# DXP_LCD1602.net
KiCad netlist of a schematic drawn in Altium Designer
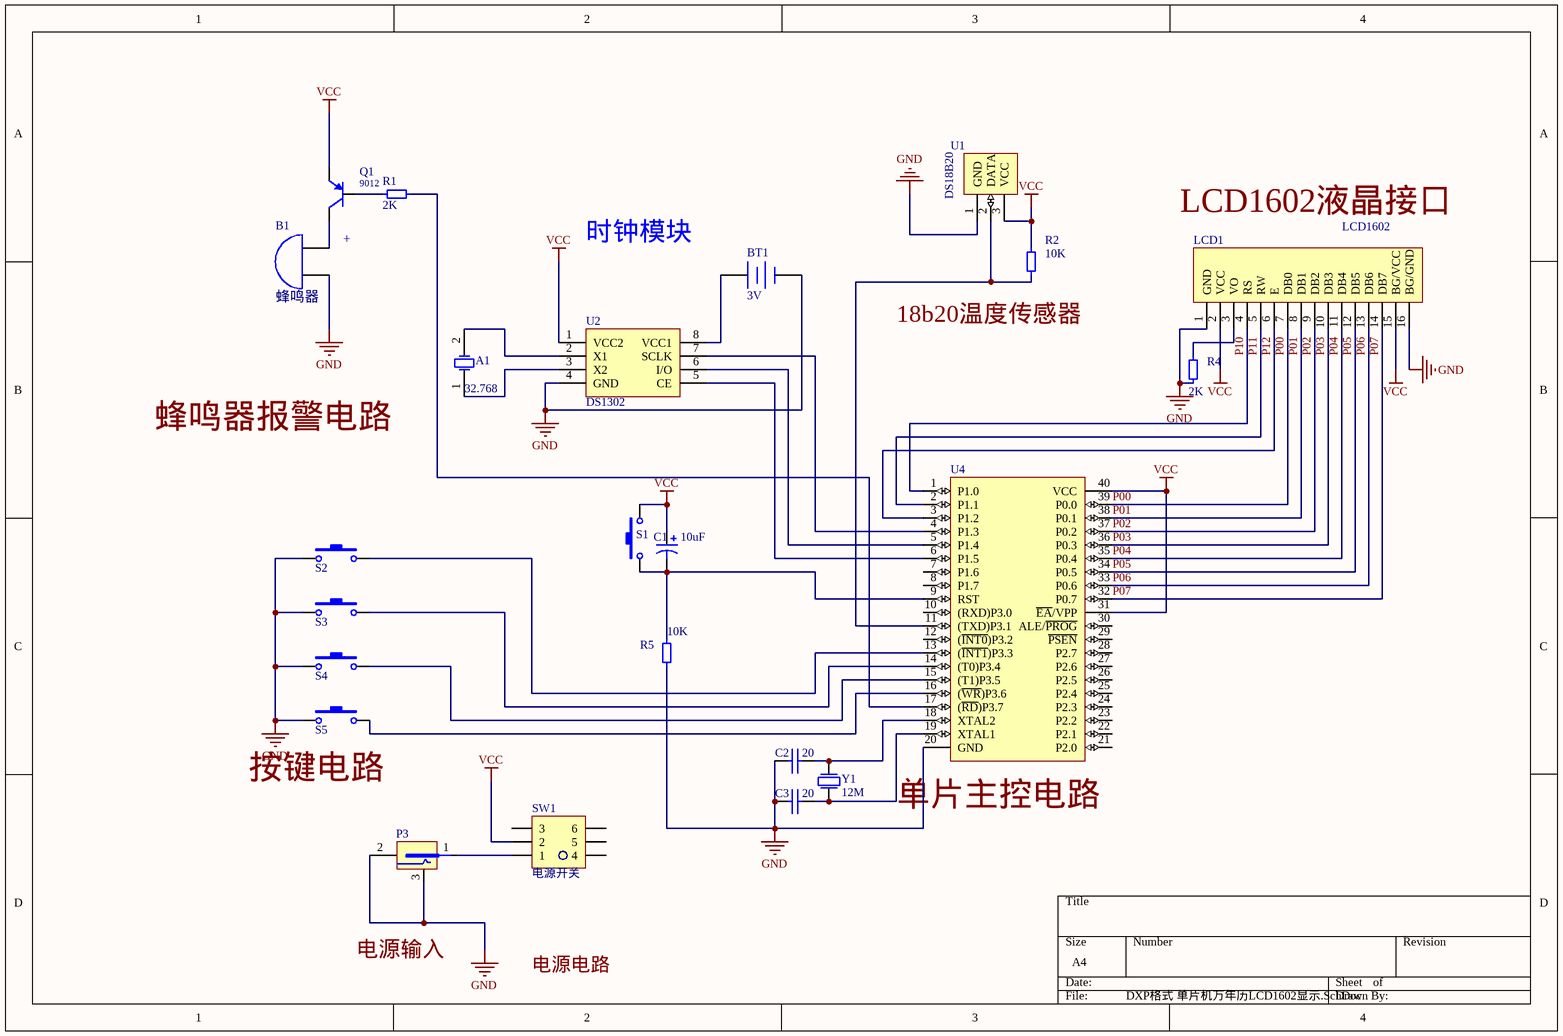
[diagram p0: DXP格式 单片机万年历LCD1602显示.SchDoc]

(export (version "E")
  (design (tool "Eeschema 10.0.6"))
  (components
    (comp (ref "A1") (value "32.768") (footprint "HDR1X2") (libsource (lib "实用原理图库") (part "XTA")))
    (comp (ref "B1")
      (value "蜂鸣器")
      (footprint "Bett")
      (description "Bell")
      (libsource (lib "实验板原理图") (part "BELL"))
    )
    (comp (ref "BT1")
      (value "3V")
      (footprint "BATT")
      (description "Multicell Battery")
      (fields (field (name "PUBLISHER") "Altium Limited"))
      (libsource (lib "Miscellaneous Devices") (part "Battery"))
    )
    (comp (ref "C1")
      (value "10uF")
      (footprint "C_10")
      (description "Polarized Capacitor (Radial)")
      (fields (field (name "PUBLISHER") "Altium Limited"))
      (libsource (lib "简易动环监控系统") (part "Cap Pol1"))
    )
    (comp (ref "C2")
      (value "20")
      (footprint "CAP5")
      (description "电容")
      (libsource (lib "C8051F020最小2") (part "CAP"))
    )
    (comp (ref "C3")
      (value "20")
      (footprint "CAP5")
      (description "电容")
      (libsource (lib "C8051F020最小2") (part "CAP"))
    )
    (comp (ref "LCD1") (value "LCD1602") (footprint "1602") (libsource (lib "实用原理图库") (part "LCD1602")))
    (comp (ref "P3") (value "电源输入") (footprint "DC2.1") (libsource (lib "我自己的") (part "POWER")))
    (comp (ref "Q1")
      (value "9012")
      (footprint "s三极管直插")
      (description "PNP General Purpose Amplifier")
      (fields (field (name "PUBLISHER") "Altium Limited"))
      (libsource (lib "实验板原理图") (part "2N3906"))
    )
    (comp (ref "R1") (value "2K") (footprint "AXIAL0.3") (libsource (lib "C8051F020最小2") (part "RES2")))
    (comp (ref "R2") (value "10K") (footprint "AXIAL0.3") (libsource (lib "C8051F020最小2") (part "RES2")))
    (comp (ref "R4") (value "2K") (footprint "AXIAL0.3") (libsource (lib "C8051F020最小2") (part "RES2")))
    (comp (ref "R5") (value "10K") (footprint "res400mil") (libsource (lib "C8051F020最小2") (part "RES2")))
    (comp (ref "S1")
      (value "SW-PB")
      (footprint "key")
      (description "Switch")
      (fields (field (name "PUBLISHER") "Altium Limited"))
      (libsource (lib "实验板原理图") (part "SW-PB"))
    )
    (comp (ref "S2")
      (value "SW-PB")
      (footprint "key")
      (description "Switch")
      (fields (field (name "PUBLISHER") "Altium Limited"))
      (libsource (lib "实验板原理图") (part "SW-PB"))
    )
    (comp (ref "S3")
      (value "SW-PB")
      (footprint "key")
      (description "Switch")
      (fields (field (name "PUBLISHER") "Altium Limited"))
      (libsource (lib "实验板原理图") (part "SW-PB"))
    )
    (comp (ref "S4")
      (value "SW-PB")
      (footprint "key")
      (description "Switch")
      (fields (field (name "PUBLISHER") "Altium Limited"))
      (libsource (lib "实验板原理图") (part "SW-PB"))
    )
    (comp (ref "S5")
      (value "SW-PB")
      (footprint "key")
      (description "Switch")
      (fields (field (name "PUBLISHER") "Altium Limited"))
      (libsource (lib "实验板原理图") (part "SW-PB"))
    )
    (comp (ref "SW1") (value "电源开关") (footprint "sw_自锁 1") (libsource (lib "我自己的") (part "SW1")))
    (comp (ref "U1") (value "DS18B20") (footprint "18B20") (libsource (lib "实验板原理图") (part "DS18B20")))
    (comp (ref "U2") (value "DS1302") (footprint "DIP8") (libsource (lib "实用原理图库") (part "DS1302")))
    (comp (ref "U4") (value "STC89C52") (footprint "DIP40 - 做板") (libsource (lib "实验板原理图") (part "U1")))
    (comp (ref "Y1")
      (value "12M")
      (footprint "XTAL")
      (description "Crystal Oscillator")
      (libsource (lib "C8051F020最小2") (part "16M"))
    )
  )
  (nets
    (net (code "3") (name "/P00") (class "Default")
      (node (ref "LCD1") (pin "7") (pinfunction "DB0_7") (pintype "passive"))
      (node (ref "U4") (pin "39") (pinfunction "P0.0_39") (pintype "bidirectional"))
    )
    (net (code "4") (name "/P01") (class "Default")
      (node (ref "LCD1") (pin "8") (pinfunction "DB1_8") (pintype "passive"))
      (node (ref "U4") (pin "38") (pinfunction "P0.1_38") (pintype "bidirectional"))
    )
    (net (code "5") (name "/P02") (class "Default")
      (node (ref "LCD1") (pin "9") (pinfunction "DB2_9") (pintype "passive"))
      (node (ref "U4") (pin "37") (pinfunction "P0.2_37") (pintype "bidirectional"))
    )
    (net (code "6") (name "/P03") (class "Default")
      (node (ref "LCD1") (pin "10") (pinfunction "DB3_10") (pintype "passive"))
      (node (ref "U4") (pin "36") (pinfunction "P0.3_36") (pintype "bidirectional"))
    )
    (net (code "7") (name "/P04") (class "Default")
      (node (ref "LCD1") (pin "11") (pinfunction "DB4_11") (pintype "passive"))
      (node (ref "U4") (pin "35") (pinfunction "P0.4_35") (pintype "bidirectional"))
    )
    (net (code "8") (name "/P05") (class "Default")
      (node (ref "LCD1") (pin "12") (pinfunction "DB5_12") (pintype "passive"))
      (node (ref "U4") (pin "34") (pinfunction "P0.5_34") (pintype "bidirectional"))
    )
    (net (code "9") (name "/P06") (class "Default")
      (node (ref "LCD1") (pin "13") (pinfunction "DB6_13") (pintype "passive"))
      (node (ref "U4") (pin "33") (pinfunction "P0.6_33") (pintype "bidirectional"))
    )
    (net (code "10") (name "/P07") (class "Default")
      (node (ref "LCD1") (pin "14") (pinfunction "DB7_14") (pintype "passive"))
      (node (ref "U4") (pin "32") (pinfunction "P0.7_32") (pintype "bidirectional"))
    )
    (net (code "11") (name "/P10") (class "Default")
      (node (ref "LCD1") (pin "4") (pinfunction "RS_4") (pintype "passive"))
      (node (ref "U4") (pin "1") (pinfunction "P1.0_1") (pintype "bidirectional"))
    )
    (net (code "12") (name "/P11") (class "Default")
      (node (ref "LCD1") (pin "5") (pinfunction "RW_5") (pintype "passive"))
      (node (ref "U4") (pin "2") (pinfunction "P1.1_2") (pintype "bidirectional"))
    )
    (net (code "13") (name "/P12") (class "Default")
      (node (ref "LCD1") (pin "6") (pinfunction "E_6") (pintype "passive"))
      (node (ref "U4") (pin "3") (pinfunction "P1.2_3") (pintype "bidirectional"))
    )
    (net (code "19") (name "GND") (class "Default")
      (node (ref "B1") (pin "2") (pinfunction "B_2") (pintype "passive"))
      (node (ref "BT1") (pin "2") (pinfunction "-_2") (pintype "passive"))
      (node (ref "C2") (pin "1") (pinfunction "1_1") (pintype "passive"))
      (node (ref "C3") (pin "1") (pinfunction "1_1") (pintype "passive"))
      (node (ref "LCD1") (pin "1") (pinfunction "GND_1") (pintype "passive"))
      (node (ref "LCD1") (pin "16") (pinfunction "BG/GND_16") (pintype "passive"))
      (node (ref "P3") (pin "2") (pintype "passive"))
      (node (ref "P3") (pin "3") (pintype "passive"))
      (node (ref "R4") (pin "2") (pinfunction "2_2") (pintype "passive"))
      (node (ref "R5") (pin "1") (pinfunction "1_1") (pintype "passive"))
      (node (ref "S2") (pin "1") (pinfunction "1_1") (pintype "passive"))
      (node (ref "S3") (pin "1") (pinfunction "1_1") (pintype "passive"))
      (node (ref "S4") (pin "1") (pinfunction "1_1") (pintype "passive"))
      (node (ref "S5") (pin "1") (pinfunction "1_1") (pintype "passive"))
      (node (ref "U1") (pin "1") (pinfunction "GND_1") (pintype "power_in"))
      (node (ref "U2") (pin "4") (pinfunction "GND_4") (pintype "passive"))
      (node (ref "U4") (pin "20") (pinfunction "GND_20") (pintype "power_in"))
    )
    (net (code "20") (name "Net-(A1-OSC1)") (class "Default")
      (node (ref "A1") (pin "1") (pinfunction "OSC1_1") (pintype "passive"))
      (node (ref "U2") (pin "3") (pinfunction "X2_3") (pintype "passive"))
    )
    (net (code "21") (name "Net-(A1-OSC2)") (class "Default")
      (node (ref "A1") (pin "2") (pinfunction "OSC2_2") (pintype "passive"))
      (node (ref "U2") (pin "2") (pinfunction "X1_2") (pintype "passive"))
    )
    (net (code "22") (name "Net-(B1-A)") (class "Default")
      (node (ref "B1") (pin "1") (pinfunction "A_1") (pintype "passive"))
      (node (ref "Q1") (pin "3") (pinfunction "C_3") (pintype "passive"))
    )
    (net (code "23") (name "Net-(BT1-+)") (class "Default")
      (node (ref "BT1") (pin "1") (pinfunction "+_1") (pintype "passive"))
      (node (ref "U2") (pin "8") (pinfunction "VCC1_8") (pintype "passive"))
    )
    (net (code "24") (name "Net-(LCD1-VO)") (class "Default")
      (node (ref "LCD1") (pin "3") (pinfunction "VO_3") (pintype "passive"))
      (node (ref "R4") (pin "1") (pinfunction "1_1") (pintype "passive"))
    )
    (net (code "25") (name "Net-(P3-Pad1)") (class "Default")
      (node (ref "P3") (pin "1") (pintype "passive"))
      (node (ref "SW1") (pin "1") (pinfunction "1_1") (pintype "passive"))
    )
    (net (code "26") (name "Net-(Q1-B)") (class "Default")
      (node (ref "Q1") (pin "2") (pinfunction "B_2") (pintype "passive"))
      (node (ref "R1") (pin "1") (pinfunction "1_1") (pintype "passive"))
    )
    (net (code "27") (name "Net-(U1-DATA)") (class "Default")
      (node (ref "R2") (pin "1") (pinfunction "1_1") (pintype "passive"))
      (node (ref "U1") (pin "2") (pinfunction "DATA_2") (pintype "bidirectional"))
      (node (ref "U4") (pin "11") (pinfunction "(TXD)P3.1_11") (pintype "bidirectional"))
    )
    (net (code "28") (name "Net-(U2-CE)") (class "Default")
      (node (ref "U2") (pin "5") (pinfunction "CE_5") (pintype "passive"))
      (node (ref "U4") (pin "6") (pinfunction "P1.5_6") (pintype "bidirectional"))
    )
    (net (code "29") (name "Net-(U2-I{slash}O)") (class "Default")
      (node (ref "U2") (pin "6") (pinfunction "I/O_6") (pintype "passive"))
      (node (ref "U4") (pin "5") (pinfunction "P1.4_5") (pintype "bidirectional"))
    )
    (net (code "30") (name "Net-(U2-SCLK)") (class "Default")
      (node (ref "U2") (pin "7") (pinfunction "SCLK_7") (pintype "passive"))
      (node (ref "U4") (pin "4") (pinfunction "P1.3_4") (pintype "bidirectional"))
    )
    (net (code "31") (name "Net-(U4-(T0)P3.4)") (class "Default")
      (node (ref "S3") (pin "2") (pinfunction "2_2") (pintype "passive"))
      (node (ref "U4") (pin "14") (pinfunction "(T0)P3.4_14") (pintype "bidirectional"))
    )
    (net (code "32") (name "Net-(U4-(T1)P3.5)") (class "Default")
      (node (ref "S4") (pin "2") (pinfunction "2_2") (pintype "passive"))
      (node (ref "U4") (pin "15") (pinfunction "(T1)P3.5_15") (pintype "bidirectional"))
    )
    (net (code "33") (name "Net-(U4-(~{INT1})P3.3)") (class "Default")
      (node (ref "S2") (pin "2") (pinfunction "2_2") (pintype "passive"))
      (node (ref "U4") (pin "13") (pinfunction "(~{INT1})P3.3_13") (pintype "bidirectional"))
    )
    (net (code "34") (name "Net-(U4-(~{RD})P3.7)") (class "Default")
      (node (ref "R1") (pin "2") (pinfunction "2_2") (pintype "passive"))
      (node (ref "U4") (pin "17") (pinfunction "(~{RD})P3.7_17") (pintype "bidirectional"))
    )
    (net (code "35") (name "Net-(U4-(~{WR})P3.6)") (class "Default")
      (node (ref "S5") (pin "2") (pinfunction "2_2") (pintype "passive"))
      (node (ref "U4") (pin "16") (pinfunction "(~{WR})P3.6_16") (pintype "bidirectional"))
    )
    (net (code "36") (name "Net-(U4-RST)") (class "Default")
      (node (ref "C1") (pin "2") (pinfunction "2_2") (pintype "passive"))
      (node (ref "R5") (pin "2") (pinfunction "2_2") (pintype "passive"))
      (node (ref "S1") (pin "1") (pinfunction "1_1") (pintype "passive"))
      (node (ref "U4") (pin "9") (pinfunction "RST_9") (pintype "bidirectional"))
    )
    (net (code "37") (name "Net-(U4-XTAL1)") (class "Default")
      (node (ref "C3") (pin "2") (pinfunction "2_2") (pintype "passive"))
      (node (ref "U4") (pin "19") (pinfunction "XTAL1_19") (pintype "bidirectional"))
      (node (ref "Y1") (pin "2") (pinfunction "P2_2") (pintype "passive"))
    )
    (net (code "38") (name "Net-(U4-XTAL2)") (class "Default")
      (node (ref "C2") (pin "2") (pinfunction "2_2") (pintype "passive"))
      (node (ref "U4") (pin "18") (pinfunction "XTAL2_18") (pintype "bidirectional"))
      (node (ref "Y1") (pin "1") (pinfunction "P1_1") (pintype "passive"))
    )
    (net (code "39") (name "VCC") (class "Default")
      (node (ref "C1") (pin "1") (pinfunction "1_1") (pintype "passive"))
      (node (ref "LCD1") (pin "15") (pinfunction "BG/VCC_15") (pintype "passive"))
      (node (ref "LCD1") (pin "2") (pinfunction "VCC_2") (pintype "passive"))
      (node (ref "Q1") (pin "1") (pinfunction "E_1") (pintype "passive"))
      (node (ref "R2") (pin "2") (pinfunction "2_2") (pintype "passive"))
      (node (ref "S1") (pin "2") (pinfunction "2_2") (pintype "passive"))
      (node (ref "SW1") (pin "2") (pinfunction "2_2") (pintype "passive"))
      (node (ref "U1") (pin "3") (pinfunction "VCC_3") (pintype "power_in"))
      (node (ref "U2") (pin "1") (pinfunction "VCC2_1") (pintype "passive"))
      (node (ref "U4") (pin "31") (pinfunction "~{EA}/VPP_31") (pintype "power_in"))
      (node (ref "U4") (pin "40") (pinfunction "VCC_40") (pintype "power_in"))
    )
    (net (code "40") (name "unconnected-(SW1-Pad3)") (class "Default")
      (node (ref "SW1") (pin "3") (pinfunction "3_3") (pintype "passive"))
    )
    (net (code "41") (name "unconnected-(SW1-Pad4)") (class "Default")
      (node (ref "SW1") (pin "4") (pinfunction "4_4") (pintype "passive"))
    )
    (net (code "42") (name "unconnected-(SW1-Pad5)") (class "Default")
      (node (ref "SW1") (pin "5") (pinfunction "5_5") (pintype "passive"))
    )
    (net (code "43") (name "unconnected-(SW1-Pad6)") (class "Default")
      (node (ref "SW1") (pin "6") (pinfunction "6_6") (pintype "passive"))
    )
    (net (code "44") (name "unconnected-(U4-(RXD)P3.0-Pad10)") (class "Default")
      (node (ref "U4") (pin "10") (pinfunction "(RXD)P3.0_10") (pintype "bidirectional"))
    )
    (net (code "45") (name "unconnected-(U4-(~{INT0})P3.2-Pad12)") (class "Default")
      (node (ref "U4") (pin "12") (pinfunction "(~{INT0})P3.2_12") (pintype "bidirectional"))
    )
    (net (code "46") (name "unconnected-(U4-ALE{slash}~{PROG}-Pad30)") (class "Default")
      (node (ref "U4") (pin "30") (pinfunction "ALE/~{PROG}_30") (pintype "bidirectional"))
    )
    (net (code "47") (name "unconnected-(U4-P1.6-Pad7)") (class "Default")
      (node (ref "U4") (pin "7") (pinfunction "P1.6_7") (pintype "bidirectional"))
    )
    (net (code "48") (name "unconnected-(U4-P1.7-Pad8)") (class "Default")
      (node (ref "U4") (pin "8") (pinfunction "P1.7_8") (pintype "bidirectional"))
    )
    (net (code "49") (name "unconnected-(U4-P2.0-Pad21)") (class "Default")
      (node (ref "U4") (pin "21") (pinfunction "P2.0_21") (pintype "bidirectional"))
    )
    (net (code "50") (name "unconnected-(U4-P2.1-Pad22)") (class "Default")
      (node (ref "U4") (pin "22") (pinfunction "P2.1_22") (pintype "bidirectional"))
    )
    (net (code "51") (name "unconnected-(U4-P2.2-Pad23)") (class "Default")
      (node (ref "U4") (pin "23") (pinfunction "P2.2_23") (pintype "bidirectional"))
    )
    (net (code "52") (name "unconnected-(U4-P2.3-Pad24)") (class "Default")
      (node (ref "U4") (pin "24") (pinfunction "P2.3_24") (pintype "bidirectional"))
    )
    (net (code "53") (name "unconnected-(U4-P2.4-Pad25)") (class "Default")
      (node (ref "U4") (pin "25") (pinfunction "P2.4_25") (pintype "bidirectional"))
    )
    (net (code "54") (name "unconnected-(U4-P2.5-Pad26)") (class "Default")
      (node (ref "U4") (pin "26") (pinfunction "P2.5_26") (pintype "bidirectional"))
    )
    (net (code "55") (name "unconnected-(U4-P2.6-Pad27)") (class "Default")
      (node (ref "U4") (pin "27") (pinfunction "P2.6_27") (pintype "bidirectional"))
    )
    (net (code "56") (name "unconnected-(U4-P2.7-Pad28)") (class "Default")
      (node (ref "U4") (pin "28") (pinfunction "P2.7_28") (pintype "bidirectional"))
    )
    (net (code "57") (name "unconnected-(U4-~{PSEN}-Pad29)") (class "Default")
      (node (ref "U4") (pin "29") (pinfunction "~{PSEN}_29") (pintype "bidirectional"))
    )
  )
)
